# Esquema.net
KiCad netlist of a schematic drawn in EAGLE
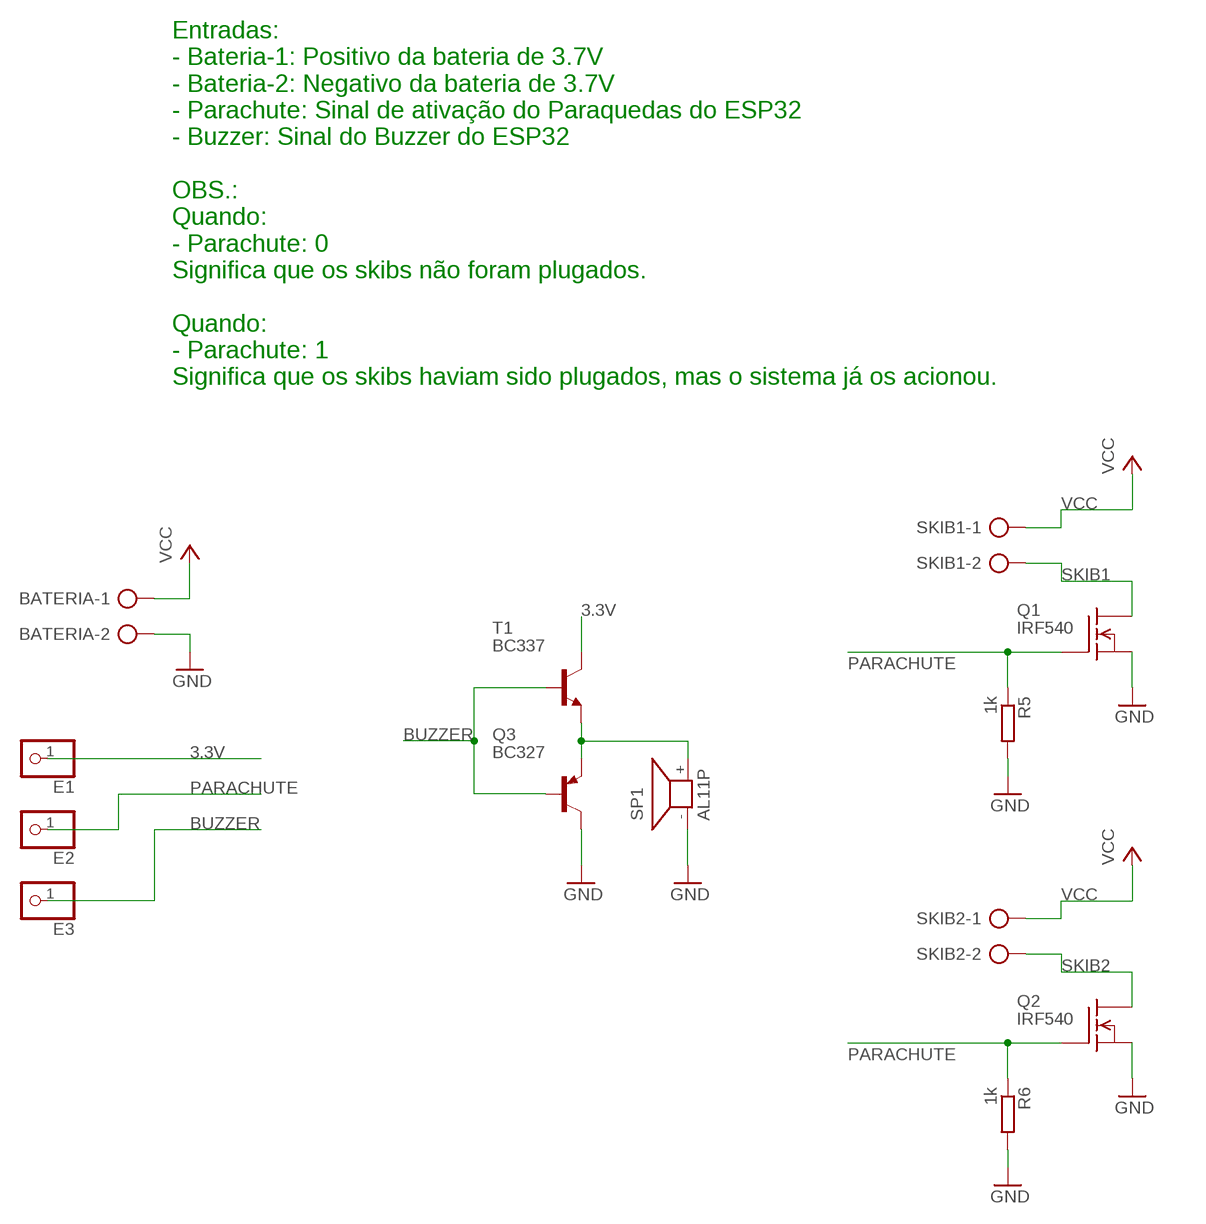
[diagram p0: schematic, sheet 1]

(export (version "E")
  (design (tool "Eeschema 10.0.6"))
  (components
    (comp (ref "BATERIA")
      (value "AK500/2-H")
      (footprint "eagle-import:AK500_2-H")
      (libsource (lib "eagle-import") (part "AK500/2-H"))
    )
    (comp (ref "E1")
      (value "PINHD-1X1")
      (footprint "eagle-import:1X01")
      (libsource (lib "eagle-import") (part "PINHD-1X1"))
    )
    (comp (ref "E2")
      (value "PINHD-1X1")
      (footprint "eagle-import:1X01")
      (libsource (lib "eagle-import") (part "PINHD-1X1"))
    )
    (comp (ref "E3")
      (value "PINHD-1X1")
      (footprint "eagle-import:1X01")
      (libsource (lib "eagle-import") (part "PINHD-1X1"))
    )
    (comp (ref "Q1")
      (value "IRF540")
      (footprint "eagle-import:TO220")
      (libsource (lib "eagle-import") (part "IRF540"))
    )
    (comp (ref "Q2")
      (value "IRF540")
      (footprint "eagle-import:TO220")
      (libsource (lib "eagle-import") (part "IRF540"))
    )
    (comp (ref "Q3")
      (value "BC327")
      (footprint "eagle-import:TO92")
      (libsource (lib "eagle-import") (part "BC327"))
    )
    (comp (ref "R5")
      (value "1k")
      (footprint "eagle-import:0207_10")
      (libsource (lib "eagle-import") (part "R-EU_0207/10"))
    )
    (comp (ref "R6")
      (value "1k")
      (footprint "eagle-import:0207_10")
      (libsource (lib "eagle-import") (part "R-EU_0207/10"))
    )
    (comp (ref "SKIB1")
      (value "AK500/2-H")
      (footprint "eagle-import:AK500_2-H")
      (libsource (lib "eagle-import") (part "AK500/2-H"))
    )
    (comp (ref "SKIB2")
      (value "AK500/2-H")
      (footprint "eagle-import:AK500_2-H")
      (libsource (lib "eagle-import") (part "AK500/2-H"))
    )
    (comp (ref "SP1")
      (value "AL11P")
      (footprint "eagle-import:AL11P")
      (libsource (lib "eagle-import") (part "AL11P"))
    )
    (comp (ref "T1")
      (value "BC337")
      (footprint "eagle-import:TO92")
      (libsource (lib "eagle-import") (part "BC337"))
    )
  )
  (nets
    (net (code "1") (name "/3.3V") (class "Default")
      (node (ref "E1") (pin "1") (pinfunction "1_1") (pintype "passive"))
      (node (ref "T1") (pin "3") (pinfunction "C_3") (pintype "passive"))
    )
    (net (code "2") (name "/BUZZER") (class "Default")
      (node (ref "E3") (pin "1") (pinfunction "1_1") (pintype "passive"))
      (node (ref "Q3") (pin "2") (pinfunction "B_2") (pintype "passive"))
      (node (ref "T1") (pin "2") (pinfunction "B_2") (pintype "passive"))
    )
    (net (code "3") (name "/PARACHUTE") (class "Default")
      (node (ref "E2") (pin "1") (pinfunction "1_1") (pintype "passive"))
      (node (ref "Q1") (pin "1") (pinfunction "G_1") (pintype "passive"))
      (node (ref "Q2") (pin "1") (pinfunction "G_1") (pintype "passive"))
      (node (ref "R5") (pin "1") (pinfunction "1_1") (pintype "passive"))
      (node (ref "R6") (pin "1") (pinfunction "1_1") (pintype "passive"))
    )
    (net (code "4") (name "/SKIB1") (class "Default")
      (node (ref "Q1") (pin "2") (pinfunction "D_2") (pintype "passive"))
      (node (ref "SKIB1") (pin "2") (pinfunction "KL_2") (pintype "passive"))
    )
    (net (code "5") (name "/SKIB2") (class "Default")
      (node (ref "Q2") (pin "2") (pinfunction "D_2") (pintype "passive"))
      (node (ref "SKIB2") (pin "2") (pinfunction "KL_2") (pintype "passive"))
    )
    (net (code "6") (name "GND") (class "Default")
      (node (ref "BATERIA") (pin "2") (pinfunction "KL_2") (pintype "passive"))
      (node (ref "Q1") (pin "3") (pinfunction "S_3") (pintype "passive"))
      (node (ref "Q2") (pin "3") (pinfunction "S_3") (pintype "passive"))
      (node (ref "Q3") (pin "3") (pinfunction "C_3") (pintype "passive"))
      (node (ref "R5") (pin "2") (pinfunction "2_2") (pintype "passive"))
      (node (ref "R6") (pin "2") (pinfunction "2_2") (pintype "passive"))
      (node (ref "SP1") (pin "-") (pinfunction "1_-") (pintype "passive"))
    )
    (net (code "7") (name "Net-(Q3-E)") (class "Default")
      (node (ref "Q3") (pin "1") (pinfunction "E_1") (pintype "passive"))
      (node (ref "SP1") (pin "+") (pinfunction "2_+") (pintype "passive"))
      (node (ref "T1") (pin "1") (pinfunction "E_1") (pintype "passive"))
    )
    (net (code "8") (name "VCC") (class "Default")
      (node (ref "BATERIA") (pin "1") (pinfunction "KL_1") (pintype "passive"))
      (node (ref "SKIB1") (pin "1") (pinfunction "KL_1") (pintype "passive"))
      (node (ref "SKIB2") (pin "1") (pinfunction "KL_1") (pintype "passive"))
    )
  )
)
